# Sheet1.net
KiCad netlist of a schematic drawn in Altium Designer
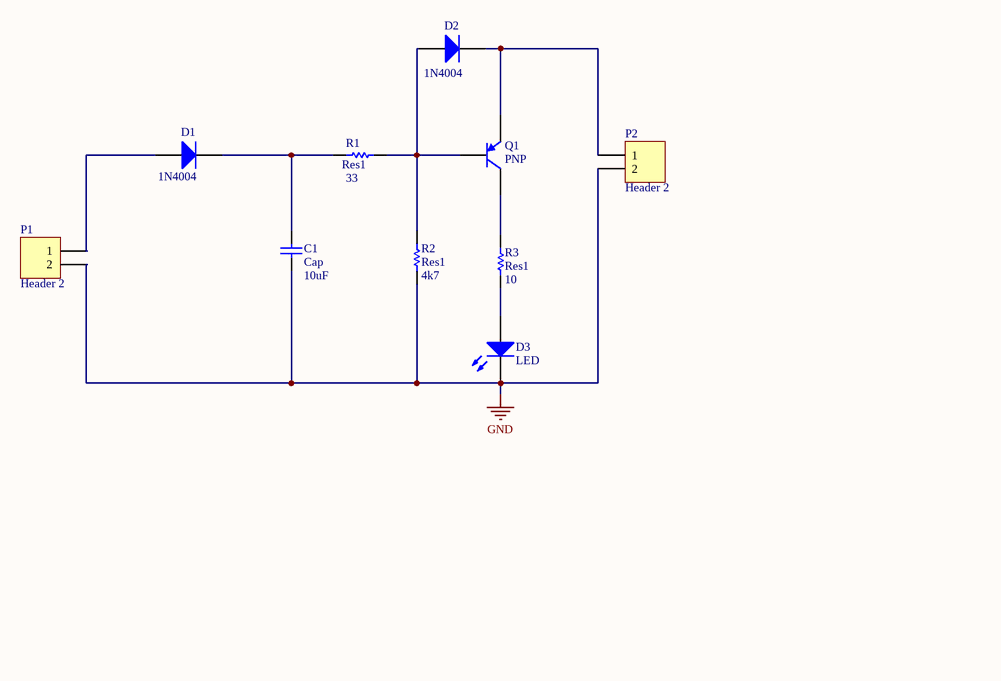
[diagram p0: Sheet1.SchDoc]

(export (version "E")
  (design (tool "Eeschema 10.0.6"))
  (components
    (comp (ref "C1")
      (value "Cap")
      (footprint "KONDENZATOR")
      (description "Capacitor")
      (fields (field (name "ALTIUM_VALUE") "10uF") (field (name "PUBLISHER") "Altium Limited"))
      (libsource (lib "Miscellaneous Devices") (part "Cap"))
    )
    (comp (ref "D1")
      (value "1N4004")
      (footprint "DIODE")
      (description "1 Amp General Purpose Rectifier")
      (fields (field (name "PUBLISHER") "Altium Limited"))
      (libsource (lib "Miscellaneous Devices") (part "Diode 1N4004"))
    )
    (comp (ref "D2")
      (value "1N4004")
      (footprint "DIODE")
      (description "1 Amp General Purpose Rectifier")
      (fields (field (name "PUBLISHER") "Altium Limited"))
      (libsource (lib "Miscellaneous Devices") (part "Diode 1N4004"))
    )
    (comp (ref "D3")
      (value "LED")
      (footprint "LED DIODA")
      (description "Typical RED GaAs LED")
      (fields (field (name "PUBLISHER") "Altium Limited"))
      (libsource (lib "Miscellaneous Devices") (part "LED1"))
    )
    (comp (ref "P1")
      (value "Header 2")
      (footprint "HDR1X2")
      (description "Header, 2-Pin")
      (fields (field (name "PUBLISHER") "Altium Limited"))
      (libsource (lib "Miscellaneous Connectors") (part "Header 2"))
    )
    (comp (ref "P2")
      (value "Header 2")
      (footprint "HDR1X2")
      (description "Header, 2-Pin")
      (fields (field (name "PUBLISHER") "Altium Limited"))
      (libsource (lib "") (part "Header 2_1"))
    )
    (comp (ref "Q1")
      (value "PNP")
      (footprint "PNP")
      (description "PNP General Purpose Amplifier")
      (fields (field (name "PUBLISHER") "Altium Limited"))
      (libsource (lib "Miscellaneous Devices") (part "2N3906"))
    )
    (comp (ref "R1")
      (value "Res1")
      (footprint "OTPORNIK")
      (description "Resistor")
      (fields (field (name "ALTIUM_VALUE") "33") (field (name "PUBLISHER") "Altium Limited"))
      (libsource (lib "PcbLib1") (part "Res1"))
    )
    (comp (ref "R2")
      (value "Res1")
      (footprint "OTPORNIK")
      (description "Resistor")
      (fields (field (name "ALTIUM_VALUE") "4k7") (field (name "PUBLISHER") "Altium Limited"))
      (libsource (lib "PcbLib1") (part "Res1"))
    )
    (comp (ref "R3")
      (value "Res1")
      (footprint "OTPORNIK")
      (description "Resistor")
      (fields (field (name "ALTIUM_VALUE") "10") (field (name "PUBLISHER") "Altium Limited"))
      (libsource (lib "PcbLib1") (part "Res1"))
    )
  )
  (nets
    (net (code "1") (name "GND") (class "Default")
      (node (ref "C1") (pin "1") (pinfunction "1_1") (pintype "passive"))
      (node (ref "D3") (pin "2") (pinfunction "K_2") (pintype "passive"))
      (node (ref "P1") (pin "2") (pinfunction "2_2") (pintype "passive"))
      (node (ref "P2") (pin "2") (pinfunction "2_2") (pintype "passive"))
      (node (ref "R2") (pin "1") (pinfunction "1_1") (pintype "passive"))
    )
    (net (code "2") (name "Net-(D1-A)") (class "Default")
      (node (ref "D1") (pin "1") (pinfunction "A_1") (pintype "passive"))
      (node (ref "P1") (pin "1") (pinfunction "1_1") (pintype "passive"))
    )
    (net (code "3") (name "Net-(D1-K)") (class "Default")
      (node (ref "C1") (pin "2") (pinfunction "2_2") (pintype "passive"))
      (node (ref "D1") (pin "2") (pinfunction "K_2") (pintype "passive"))
      (node (ref "R1") (pin "1") (pinfunction "1_1") (pintype "passive"))
    )
    (net (code "4") (name "Net-(D2-A)") (class "Default")
      (node (ref "D2") (pin "1") (pinfunction "A_1") (pintype "passive"))
      (node (ref "Q1") (pin "2") (pinfunction "B_2") (pintype "passive"))
      (node (ref "R1") (pin "2") (pinfunction "2_2") (pintype "passive"))
      (node (ref "R2") (pin "2") (pinfunction "2_2") (pintype "passive"))
    )
    (net (code "5") (name "Net-(D2-K)") (class "Default")
      (node (ref "D2") (pin "2") (pinfunction "K_2") (pintype "passive"))
      (node (ref "P2") (pin "1") (pinfunction "1_1") (pintype "passive"))
      (node (ref "Q1") (pin "3") (pinfunction "E_3") (pintype "passive"))
    )
    (net (code "6") (name "Net-(D3-A)") (class "Default")
      (node (ref "D3") (pin "1") (pinfunction "A_1") (pintype "passive"))
      (node (ref "R3") (pin "1") (pinfunction "1_1") (pintype "passive"))
    )
    (net (code "7") (name "Net-(Q1-C)") (class "Default")
      (node (ref "Q1") (pin "1") (pinfunction "C_1") (pintype "passive"))
      (node (ref "R3") (pin "2") (pinfunction "2_2") (pintype "passive"))
    )
  )
)
